# MRCS-Optical-Detector.net
KiCad netlist of a schematic drawn in EAGLE
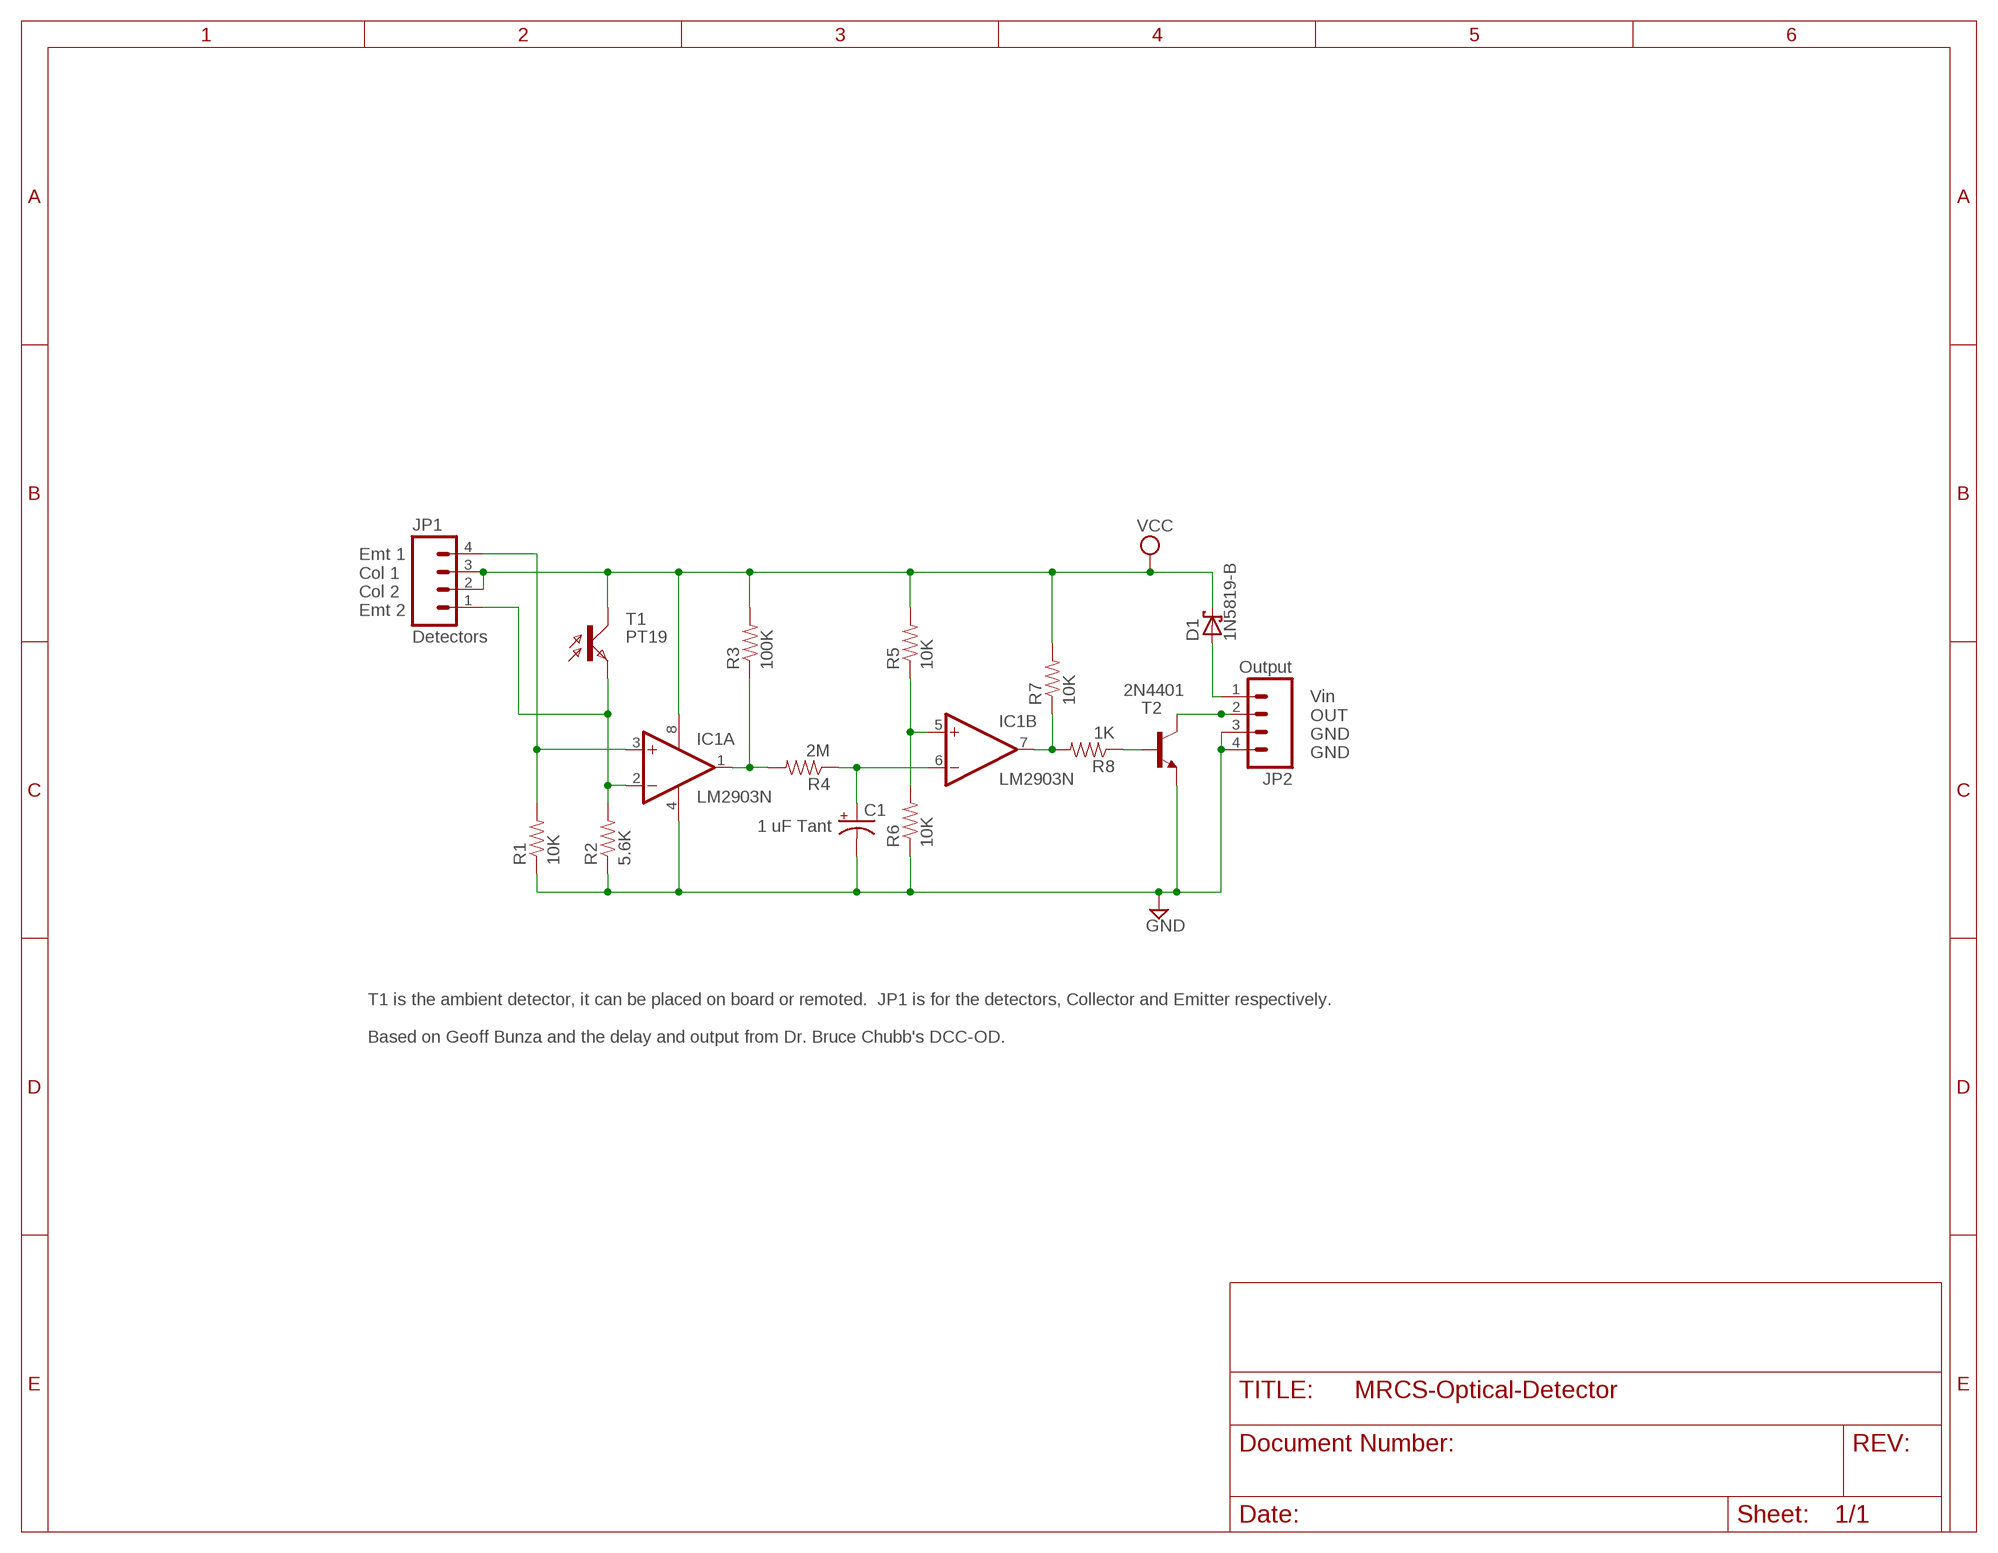
[diagram p0: schematic, sheet 1]

(export (version "E")
  (design (tool "Eeschema 10.0.6"))
  (components
    (comp (ref "C1")
      (value "1 uF Tant")
      (footprint "eagle-import:E2.5-5")
      (libsource (lib "eagle-import") (part "CPOL-USE2.5-5"))
    )
    (comp (ref "D1")
      (value "1N5819-B")
      (footprint "eagle-import:DO41-7.6")
      (libsource (lib "eagle-import") (part "1N5819-B"))
    )
    (comp (ref "IC1")
      (value "LM2903N")
      (footprint "eagle-import:DIL08")
      (libsource (lib "eagle-import") (part "LM2903N"))
    )
    (comp (ref "JP1")
      (value "Detectors")
      (footprint "eagle-import:1X04_LOCK")
      (libsource (lib "eagle-import") (part "M04LOCK"))
    )
    (comp (ref "JP2")
      (value "Output")
      (footprint "eagle-import:1X04_LOCK")
      (libsource (lib "eagle-import") (part "M04LOCK"))
    )
    (comp (ref "R1")
      (value "10K")
      (footprint "eagle-import:AXIAL-0.4")
      (libsource (lib "eagle-import") (part "RESISTORPTH-1/4W"))
    )
    (comp (ref "R2")
      (value "5.6K")
      (footprint "eagle-import:AXIAL-0.4")
      (libsource (lib "eagle-import") (part "RESISTORPTH-1/4W"))
    )
    (comp (ref "R3")
      (value "100K")
      (footprint "eagle-import:AXIAL-0.4")
      (libsource (lib "eagle-import") (part "RESISTORPTH-1/4W"))
    )
    (comp (ref "R4")
      (value "2M")
      (footprint "eagle-import:AXIAL-0.4")
      (libsource (lib "eagle-import") (part "RESISTORPTH-1/4W"))
    )
    (comp (ref "R5")
      (value "10K")
      (footprint "eagle-import:AXIAL-0.4")
      (libsource (lib "eagle-import") (part "RESISTORPTH-1/4W"))
    )
    (comp (ref "R6")
      (value "10K")
      (footprint "eagle-import:AXIAL-0.4")
      (libsource (lib "eagle-import") (part "RESISTORPTH-1/4W"))
    )
    (comp (ref "R7")
      (value "10K")
      (footprint "eagle-import:AXIAL-0.4")
      (libsource (lib "eagle-import") (part "RESISTORPTH-1/4W"))
    )
    (comp (ref "R8")
      (value "1K")
      (footprint "eagle-import:AXIAL-0.4")
      (libsource (lib "eagle-import") (part "RESISTORPTH-1/4W"))
    )
    (comp (ref "T1")
      (value "PT19")
      (footprint "eagle-import:BPX81")
      (libsource (lib "eagle-import") (part "BPX81"))
    )
    (comp (ref "T2")
      (value "2N4401")
      (footprint "eagle-import:TO92-EBC")
      (libsource (lib "eagle-import") (part "-NPN-TO92-EBC2N3904"))
    )
  )
  (nets
    (net (code "1") (name "GND") (class "Default")
      (node (ref "C1") (pin "-") (pinfunction "-_-") (pintype "passive"))
      (node (ref "IC1") (pin "4") (pinfunction "V-_4") (pintype "power_in"))
      (node (ref "JP2") (pin "3") (pinfunction "3_3") (pintype "passive"))
      (node (ref "JP2") (pin "4") (pinfunction "4_4") (pintype "passive"))
      (node (ref "R1") (pin "P$1") (pinfunction "1_P$1") (pintype "passive"))
      (node (ref "R2") (pin "P$1") (pinfunction "1_P$1") (pintype "passive"))
      (node (ref "R6") (pin "P$1") (pinfunction "1_P$1") (pintype "passive"))
      (node (ref "T2") (pin "E") (pinfunction "E_E") (pintype "passive"))
    )
    (net (code "2") (name "Net-(D1-PadA)") (class "Default")
      (node (ref "D1") (pin "A") (pinfunction "A_A") (pintype "passive"))
      (node (ref "JP2") (pin "1") (pinfunction "1_1") (pintype "passive"))
    )
    (net (code "3") (name "Net-(IC1A-+IN)") (class "Default")
      (node (ref "IC1") (pin "3") (pinfunction "+IN_3") (pintype "input"))
      (node (ref "JP1") (pin "4") (pinfunction "4_4") (pintype "passive"))
      (node (ref "R1") (pin "P$2") (pinfunction "2_P$2") (pintype "passive"))
    )
    (net (code "4") (name "Net-(IC1A--IN)") (class "Default")
      (node (ref "IC1") (pin "2") (pinfunction "-IN_2") (pintype "input"))
      (node (ref "JP1") (pin "1") (pinfunction "1_1") (pintype "passive"))
      (node (ref "R2") (pin "P$2") (pinfunction "2_P$2") (pintype "passive"))
      (node (ref "T1") (pin "E") (pinfunction "E_E") (pintype "passive"))
    )
    (net (code "5") (name "Net-(IC1A-OUT)") (class "Default")
      (node (ref "IC1") (pin "1") (pinfunction "OUT_1") (pintype "output"))
      (node (ref "R3") (pin "P$1") (pinfunction "1_P$1") (pintype "passive"))
      (node (ref "R4") (pin "P$2") (pinfunction "2_P$2") (pintype "passive"))
    )
    (net (code "6") (name "Net-(IC1B-+IN)") (class "Default")
      (node (ref "IC1") (pin "5") (pinfunction "+IN_5") (pintype "input"))
      (node (ref "R5") (pin "P$1") (pinfunction "1_P$1") (pintype "passive"))
      (node (ref "R6") (pin "P$2") (pinfunction "2_P$2") (pintype "passive"))
    )
    (net (code "7") (name "Net-(IC1B--IN)") (class "Default")
      (node (ref "C1") (pin "+") (pinfunction "+_+") (pintype "passive"))
      (node (ref "IC1") (pin "6") (pinfunction "-IN_6") (pintype "input"))
      (node (ref "R4") (pin "P$1") (pinfunction "1_P$1") (pintype "passive"))
    )
    (net (code "8") (name "Net-(IC1B-OUT)") (class "Default")
      (node (ref "IC1") (pin "7") (pinfunction "OUT_7") (pintype "output"))
      (node (ref "R7") (pin "P$1") (pinfunction "1_P$1") (pintype "passive"))
      (node (ref "R8") (pin "P$2") (pinfunction "2_P$2") (pintype "passive"))
    )
    (net (code "9") (name "Net-(JP2-Pad2)") (class "Default")
      (node (ref "JP2") (pin "2") (pinfunction "2_2") (pintype "passive"))
      (node (ref "T2") (pin "C") (pinfunction "C_C") (pintype "passive"))
    )
    (net (code "10") (name "Net-(R8-1)") (class "Default")
      (node (ref "R8") (pin "P$1") (pinfunction "1_P$1") (pintype "passive"))
      (node (ref "T2") (pin "B") (pinfunction "B_B") (pintype "passive"))
    )
    (net (code "11") (name "VCC") (class "Default")
      (node (ref "D1") (pin "C") (pinfunction "C_C") (pintype "passive"))
      (node (ref "IC1") (pin "8") (pinfunction "V+_8") (pintype "power_in"))
      (node (ref "JP1") (pin "2") (pinfunction "2_2") (pintype "passive"))
      (node (ref "JP1") (pin "3") (pinfunction "3_3") (pintype "passive"))
      (node (ref "R3") (pin "P$2") (pinfunction "2_P$2") (pintype "passive"))
      (node (ref "R5") (pin "P$2") (pinfunction "2_P$2") (pintype "passive"))
      (node (ref "R7") (pin "P$2") (pinfunction "2_P$2") (pintype "passive"))
      (node (ref "T1") (pin "C") (pinfunction "C_C") (pintype "passive"))
    )
  )
)
